# teste3.net
KiCad netlist of a schematic drawn in EAGLE
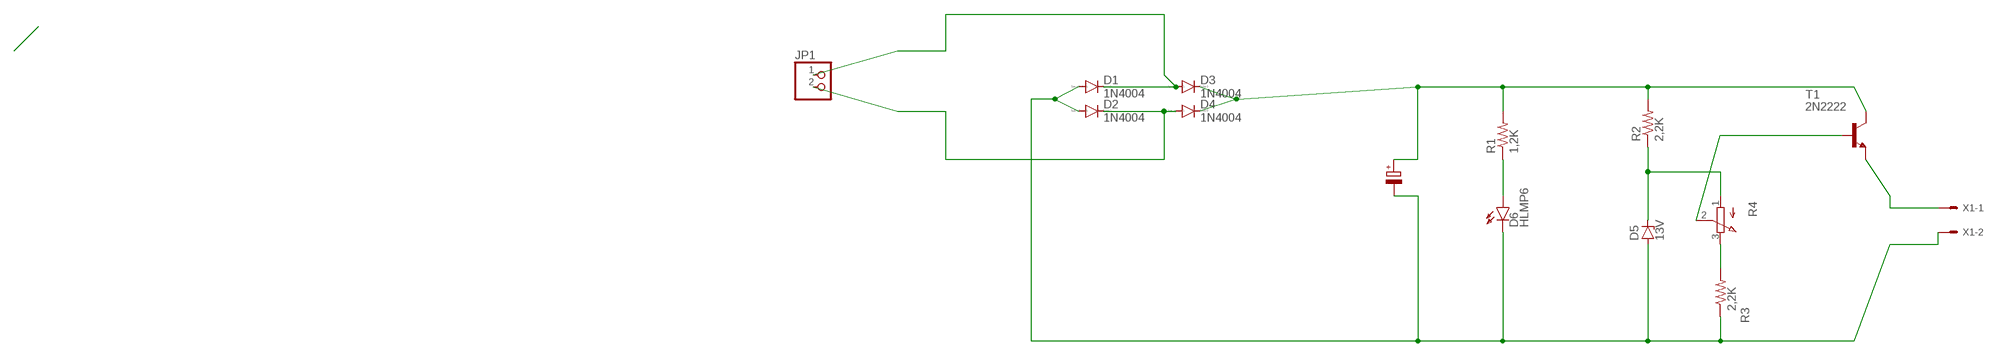
[diagram p0: schematic, sheet 1]

(export (version "E")
  (design (tool "Eeschema 10.0.6"))
  (components
    (comp (ref "D1")
      (value "1N4004")
      (footprint "eagle-import:DO41-10")
      (libsource (lib "eagle-import") (part "1N4004"))
    )
    (comp (ref "D2")
      (value "1N4004")
      (footprint "eagle-import:DO41-10")
      (libsource (lib "eagle-import") (part "1N4004"))
    )
    (comp (ref "D3")
      (value "1N4004")
      (footprint "eagle-import:DO41-10")
      (libsource (lib "eagle-import") (part "1N4004"))
    )
    (comp (ref "D4")
      (value "1N4004")
      (footprint "eagle-import:DO41-10")
      (libsource (lib "eagle-import") (part "1N4004"))
    )
    (comp (ref "D5")
      (value "13V")
      (footprint "eagle-import:SOD81")
      (libsource (lib "eagle-import") (part "BZD23"))
    )
    (comp (ref "D6")
      (value "HLMP6")
      (footprint "eagle-import:HLMP6")
      (fields (field (name "MF") "AGILENT TECHNOLOGIES") (field (name "MPN") "HLMP-6500"))
      (libsource (lib "eagle-import") (part "HLMP6"))
    )
    (comp (ref "JP1")
      (value "PINHD-1X2")
      (footprint "eagle-import:1X02")
      (libsource (lib "eagle-import") (part "PINHD-1X2"))
    )
    (comp (ref "R1")
      (value "1,2K")
      (footprint "eagle-import:P0613_15")
      (libsource (lib "eagle-import") (part "R-US_0613/15"))
    )
    (comp (ref "R2")
      (value "2,2K")
      (footprint "eagle-import:P0613_15")
      (libsource (lib "eagle-import") (part "R-US_0613/15"))
    )
    (comp (ref "R3")
      (value "2,2K")
      (footprint "eagle-import:P0613_15")
      (libsource (lib "eagle-import") (part "R-US_0613/15"))
    )
    (comp (ref "R4")
      (value "3RP/1610N")
      (footprint "eagle-import:3RP_1610N")
      (libsource (lib "eagle-import") (part "3RP/1610N"))
    )
    (comp (ref "T1")
      (value "2N2222")
      (footprint "eagle-import:TO18")
      (libsource (lib "eagle-import") (part "2N2222"))
    )
    (comp (ref "X1")
      (value "KK-156-2")
      (footprint "eagle-import:KK-156-2")
      (fields (field (name "MF") "MOLEX"))
      (libsource (lib "eagle-import") (part "KK-156-2"))
    )
  )
  (nets
    (net (code "1") (name "Net-(D1-PadC)") (class "Default")
      (node (ref "D1") (pin "C") (pinfunction "C_C") (pintype "passive"))
      (node (ref "D3") (pin "A") (pinfunction "A_A") (pintype "passive"))
      (node (ref "JP1") (pin "1") (pinfunction "1_1") (pintype "passive"))
    )
    (net (code "2") (name "Net-(D2-PadC)") (class "Default")
      (node (ref "D2") (pin "C") (pinfunction "C_C") (pintype "passive"))
      (node (ref "D4") (pin "A") (pinfunction "A_A") (pintype "passive"))
      (node (ref "JP1") (pin "2") (pinfunction "2_2") (pintype "passive"))
    )
    (net (code "3") (name "Net-(D6-PadA)") (class "Default")
      (node (ref "D6") (pin "A") (pinfunction "A_A") (pintype "passive"))
      (node (ref "R1") (pin "1") (pinfunction "1_1") (pintype "passive"))
    )
    (net (code "4") (name "Net-(R4-A)") (class "Default")
      (node (ref "D5") (pin "C") (pinfunction "C_C") (pintype "passive"))
      (node (ref "R2") (pin "1") (pinfunction "1_1") (pintype "passive"))
      (node (ref "R4") (pin "1") (pinfunction "A_1") (pintype "passive"))
    )
    (net (code "5") (name "Net-(R4-E)") (class "Default")
      (node (ref "R3") (pin "2") (pinfunction "2_2") (pintype "passive"))
      (node (ref "R4") (pin "3") (pinfunction "E_3") (pintype "passive"))
    )
    (net (code "6") (name "Net-(R4-S)") (class "Default")
      (node (ref "R4") (pin "2") (pinfunction "S_2") (pintype "passive"))
      (node (ref "T1") (pin "2") (pinfunction "B_2") (pintype "passive"))
    )
    (net (code "7") (name "Net-(T1-C)") (class "Default")
      (node (ref "D3") (pin "C") (pinfunction "C_C") (pintype "passive"))
      (node (ref "D4") (pin "C") (pinfunction "C_C") (pintype "passive"))
      (node (ref "R1") (pin "2") (pinfunction "2_2") (pintype "passive"))
      (node (ref "R2") (pin "2") (pinfunction "2_2") (pintype "passive"))
      (node (ref "T1") (pin "3") (pinfunction "C_3") (pintype "passive"))
    )
    (net (code "8") (name "Net-(T1-E)") (class "Default")
      (node (ref "T1") (pin "1") (pinfunction "E_1") (pintype "passive"))
      (node (ref "X1") (pin "1") (pinfunction "S_1") (pintype "passive"))
    )
    (net (code "9") (name "Net-(X1B-S)") (class "Default")
      (node (ref "D1") (pin "A") (pinfunction "A_A") (pintype "passive"))
      (node (ref "D2") (pin "A") (pinfunction "A_A") (pintype "passive"))
      (node (ref "D5") (pin "A") (pinfunction "A_A") (pintype "passive"))
      (node (ref "D6") (pin "K") (pinfunction "K_K") (pintype "passive"))
      (node (ref "R3") (pin "1") (pinfunction "1_1") (pintype "passive"))
      (node (ref "X1") (pin "2") (pinfunction "S_2") (pintype "passive"))
    )
  )
)
